# 4017-7Segment.net
KiCad netlist of a schematic drawn in EAGLE
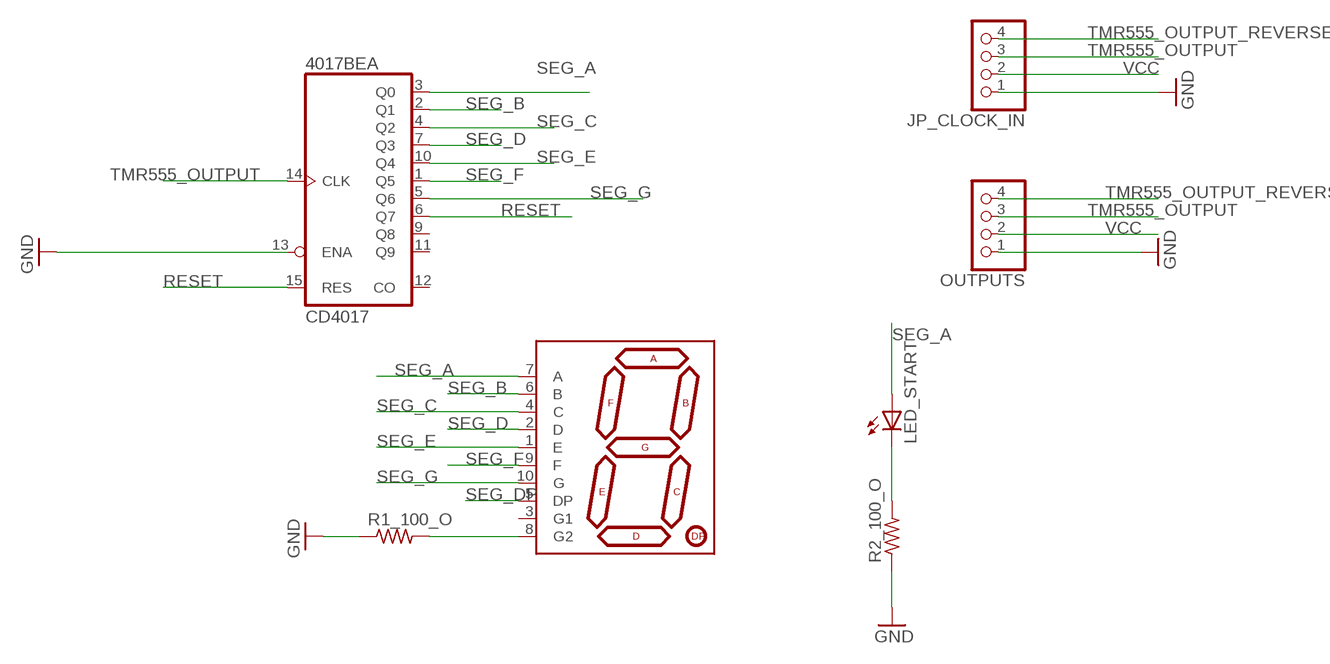
[diagram p0: schematic, sheet 1]

(export (version "E")
  (design (tool "Eeschema 10.0.6"))
  (components
    (comp (ref "4017BE")
      (value "CD4017")
      (footprint "eagle-import:DIL16")
      (libsource (lib "eagle-import") (part "CD4017"))
    )
    (comp (ref "JP_CLOCK_IN")
      (value "PINHD-1X4")
      (footprint "eagle-import:1X04")
      (libsource (lib "eagle-import") (part "PINHD-1X4"))
    )
    (comp (ref "LED_START")
      (value "LEDSMT1206")
      (footprint "eagle-import:1206")
      (libsource (lib "eagle-import") (part "LEDSMT1206"))
    )
    (comp (ref "OUTPUTS")
      (value "PINHD-1X4")
      (footprint "eagle-import:1X04")
      (libsource (lib "eagle-import") (part "PINHD-1X4"))
    )
    (comp (ref "R1_100_O")
      (value "R-US_R1206")
      (footprint "eagle-import:R1206")
      (libsource (lib "eagle-import") (part "R-US_R1206"))
    )
    (comp (ref "R2_100_O")
      (value "R-US_R1206")
      (footprint "eagle-import:R1206")
      (libsource (lib "eagle-import") (part "R-US_R1206"))
    )
    (comp (ref "U$1")
      (value "7-SEGMENT-DISPLAYPTH")
      (footprint "eagle-import:7-SEGMENT-DISPLAY")
      (libsource (lib "eagle-import") (part "7-SEGMENT-DISPLAYPTH"))
    )
  )
  (nets
    (net (code "1") (name "/RESET") (class "Default")
      (node (ref "4017BE") (pin "15") (pinfunction "RES_15") (pintype "input"))
      (node (ref "4017BE") (pin "6") (pinfunction "Q7_6") (pintype "output"))
    )
    (net (code "2") (name "/SEG_A") (class "Default")
      (node (ref "4017BE") (pin "3") (pinfunction "Q0_3") (pintype "output"))
      (node (ref "LED_START") (pin "A") (pinfunction "A_A") (pintype "passive"))
      (node (ref "U$1") (pin "7") (pinfunction "A_7") (pintype "bidirectional"))
    )
    (net (code "3") (name "/SEG_B") (class "Default")
      (node (ref "4017BE") (pin "2") (pinfunction "Q1_2") (pintype "output"))
      (node (ref "U$1") (pin "6") (pinfunction "B_6") (pintype "bidirectional"))
    )
    (net (code "4") (name "/SEG_C") (class "Default")
      (node (ref "4017BE") (pin "4") (pinfunction "Q2_4") (pintype "output"))
      (node (ref "U$1") (pin "4") (pinfunction "C_4") (pintype "bidirectional"))
    )
    (net (code "5") (name "/SEG_D") (class "Default")
      (node (ref "4017BE") (pin "7") (pinfunction "Q3_7") (pintype "output"))
      (node (ref "U$1") (pin "2") (pinfunction "D_2") (pintype "bidirectional"))
    )
    (net (code "6") (name "/SEG_DP") (class "Default")
      (node (ref "U$1") (pin "5") (pinfunction "DP_5") (pintype "bidirectional"))
    )
    (net (code "7") (name "/SEG_E") (class "Default")
      (node (ref "4017BE") (pin "10") (pinfunction "Q4_10") (pintype "output"))
      (node (ref "U$1") (pin "1") (pinfunction "E_1") (pintype "bidirectional"))
    )
    (net (code "8") (name "/SEG_F") (class "Default")
      (node (ref "4017BE") (pin "1") (pinfunction "Q5_1") (pintype "output"))
      (node (ref "U$1") (pin "9") (pinfunction "F_9") (pintype "bidirectional"))
    )
    (net (code "9") (name "/SEG_G") (class "Default")
      (node (ref "4017BE") (pin "5") (pinfunction "Q6_5") (pintype "output"))
      (node (ref "U$1") (pin "10") (pinfunction "G_10") (pintype "bidirectional"))
    )
    (net (code "10") (name "/TMR555_OUTPUT") (class "Default")
      (node (ref "4017BE") (pin "14") (pinfunction "CLK_14") (pintype "input"))
      (node (ref "JP_CLOCK_IN") (pin "3") (pinfunction "3_3") (pintype "passive"))
      (node (ref "OUTPUTS") (pin "3") (pinfunction "3_3") (pintype "passive"))
    )
    (net (code "11") (name "/TMR555_OUTPUT_REVERSE") (class "Default")
      (node (ref "JP_CLOCK_IN") (pin "4") (pinfunction "4_4") (pintype "passive"))
      (node (ref "OUTPUTS") (pin "4") (pinfunction "4_4") (pintype "passive"))
    )
    (net (code "12") (name "/VCC") (class "Default")
      (node (ref "JP_CLOCK_IN") (pin "2") (pinfunction "2_2") (pintype "passive"))
      (node (ref "OUTPUTS") (pin "2") (pinfunction "2_2") (pintype "passive"))
    )
    (net (code "13") (name "GND") (class "Default")
      (node (ref "4017BE") (pin "13") (pinfunction "ENA_13") (pintype "input"))
      (node (ref "JP_CLOCK_IN") (pin "1") (pinfunction "1_1") (pintype "passive"))
      (node (ref "OUTPUTS") (pin "1") (pinfunction "1_1") (pintype "passive"))
      (node (ref "R1_100_O") (pin "1") (pinfunction "1_1") (pintype "passive"))
      (node (ref "R2_100_O") (pin "1") (pinfunction "1_1") (pintype "passive"))
    )
    (net (code "14") (name "Net-(LED_START-PadC)") (class "Default")
      (node (ref "LED_START") (pin "C") (pinfunction "C_C") (pintype "passive"))
      (node (ref "R2_100_O") (pin "2") (pinfunction "2_2") (pintype "passive"))
    )
    (net (code "15") (name "Net-(U$1-G2)") (class "Default")
      (node (ref "R1_100_O") (pin "2") (pinfunction "2_2") (pintype "passive"))
      (node (ref "U$1") (pin "8") (pinfunction "G2_8") (pintype "bidirectional"))
    )
    (net (code "16") (name "unconnected-(4017BEA-CO-Pad12)") (class "Default")
      (node (ref "4017BE") (pin "12") (pinfunction "CO_12") (pintype "output"))
    )
    (net (code "17") (name "unconnected-(4017BEA-Q8-Pad9)") (class "Default")
      (node (ref "4017BE") (pin "9") (pinfunction "Q8_9") (pintype "output"))
    )
    (net (code "18") (name "unconnected-(4017BEA-Q9-Pad11)") (class "Default")
      (node (ref "4017BE") (pin "11") (pinfunction "Q9_11") (pintype "output"))
    )
    (net (code "19") (name "unconnected-(U$1-G1-Pad3)") (class "Default")
      (node (ref "U$1") (pin "3") (pinfunction "G1_3") (pintype "bidirectional"))
    )
  )
)
